# max10_bb.net
KiCad netlist of a schematic drawn in EAGLE
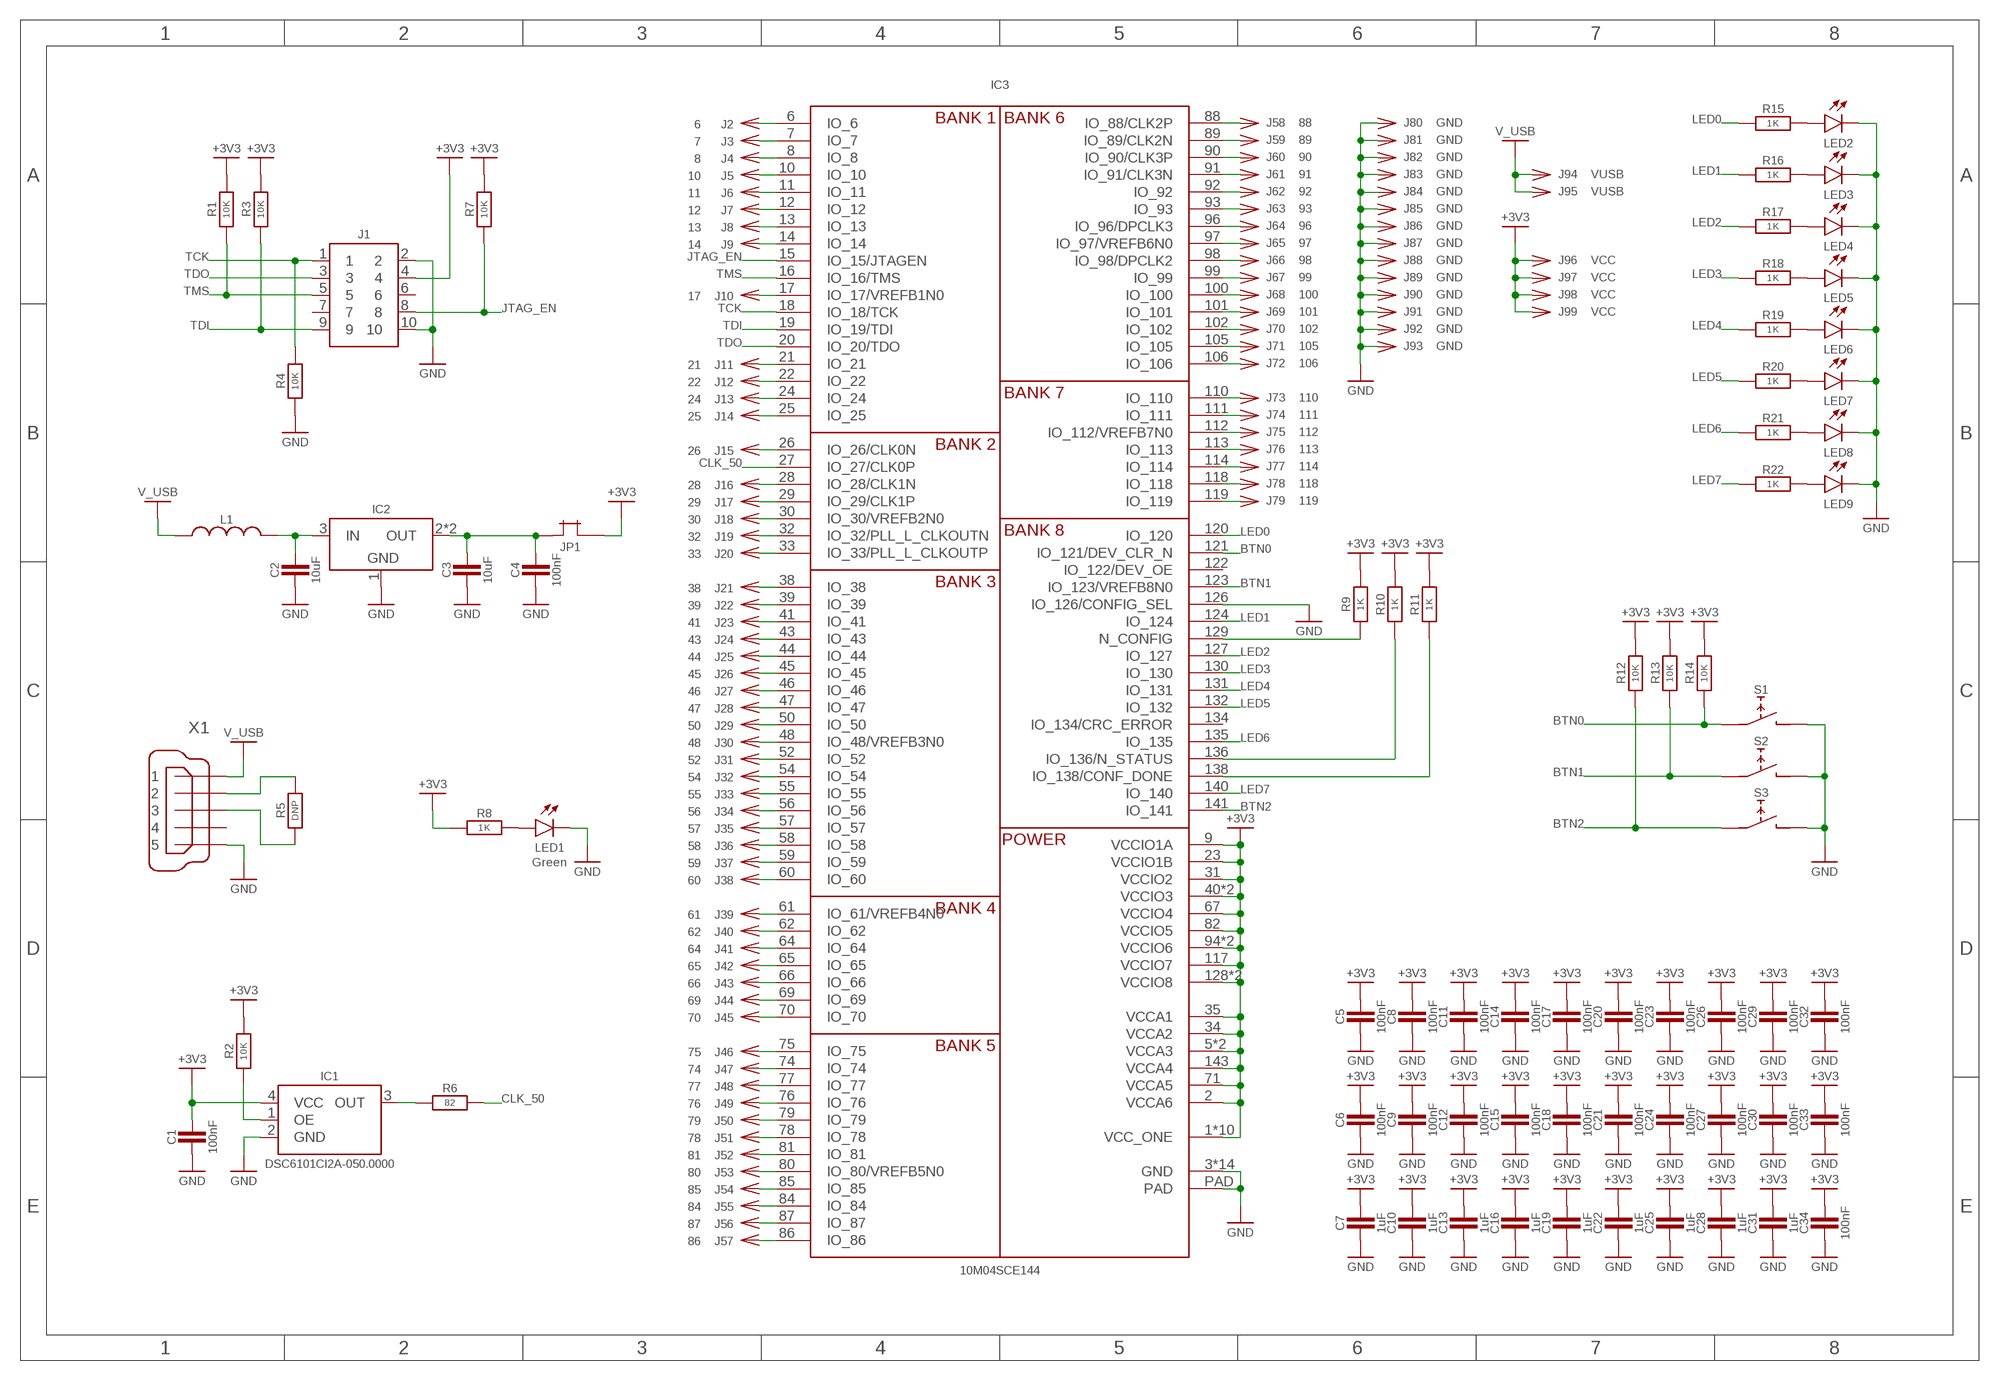
[diagram p0: schematic, sheet 1]

(export (version "E")
  (design (tool "Eeschema 10.0.6"))
  (components
    (comp (ref "C1")
      (value "100nF")
      (footprint "eagle-import:SMD0603")
      (libsource (lib "eagle-import") (part "C-0603"))
    )
    (comp (ref "C2")
      (value "10uF")
      (footprint "eagle-import:SMD0805")
      (libsource (lib "eagle-import") (part "C-0805"))
    )
    (comp (ref "C3")
      (value "10uF")
      (footprint "eagle-import:SMD0805")
      (libsource (lib "eagle-import") (part "C-0805"))
    )
    (comp (ref "C4")
      (value "100nF")
      (footprint "eagle-import:SMD0603")
      (libsource (lib "eagle-import") (part "C-0603"))
    )
    (comp (ref "C5")
      (value "100nF")
      (footprint "eagle-import:SMD0603")
      (libsource (lib "eagle-import") (part "C-0603"))
    )
    (comp (ref "C6")
      (value "100nF")
      (footprint "eagle-import:SMD0603")
      (libsource (lib "eagle-import") (part "C-0603"))
    )
    (comp (ref "C7")
      (value "1uF")
      (footprint "eagle-import:SMD0603")
      (libsource (lib "eagle-import") (part "C-0603"))
    )
    (comp (ref "C8")
      (value "100nF")
      (footprint "eagle-import:SMD0603")
      (libsource (lib "eagle-import") (part "C-0603"))
    )
    (comp (ref "C9")
      (value "100nF")
      (footprint "eagle-import:SMD0603")
      (libsource (lib "eagle-import") (part "C-0603"))
    )
    (comp (ref "C10")
      (value "1uF")
      (footprint "eagle-import:SMD0603")
      (libsource (lib "eagle-import") (part "C-0603"))
    )
    (comp (ref "C11")
      (value "100nF")
      (footprint "eagle-import:SMD0603")
      (libsource (lib "eagle-import") (part "C-0603"))
    )
    (comp (ref "C12")
      (value "100nF")
      (footprint "eagle-import:SMD0603")
      (libsource (lib "eagle-import") (part "C-0603"))
    )
    (comp (ref "C13")
      (value "1uF")
      (footprint "eagle-import:SMD0603")
      (libsource (lib "eagle-import") (part "C-0603"))
    )
    (comp (ref "C14")
      (value "100nF")
      (footprint "eagle-import:SMD0603")
      (libsource (lib "eagle-import") (part "C-0603"))
    )
    (comp (ref "C15")
      (value "100nF")
      (footprint "eagle-import:SMD0603")
      (libsource (lib "eagle-import") (part "C-0603"))
    )
    (comp (ref "C16")
      (value "1uF")
      (footprint "eagle-import:SMD0603")
      (libsource (lib "eagle-import") (part "C-0603"))
    )
    (comp (ref "C17")
      (value "100nF")
      (footprint "eagle-import:SMD0603")
      (libsource (lib "eagle-import") (part "C-0603"))
    )
    (comp (ref "C18")
      (value "100nF")
      (footprint "eagle-import:SMD0603")
      (libsource (lib "eagle-import") (part "C-0603"))
    )
    (comp (ref "C19")
      (value "1uF")
      (footprint "eagle-import:SMD0603")
      (libsource (lib "eagle-import") (part "C-0603"))
    )
    (comp (ref "C20")
      (value "100nF")
      (footprint "eagle-import:SMD0603")
      (libsource (lib "eagle-import") (part "C-0603"))
    )
    (comp (ref "C21")
      (value "100nF")
      (footprint "eagle-import:SMD0603")
      (libsource (lib "eagle-import") (part "C-0603"))
    )
    (comp (ref "C22")
      (value "1uF")
      (footprint "eagle-import:SMD0603")
      (libsource (lib "eagle-import") (part "C-0603"))
    )
    (comp (ref "C23")
      (value "100nF")
      (footprint "eagle-import:SMD0603")
      (libsource (lib "eagle-import") (part "C-0603"))
    )
    (comp (ref "C24")
      (value "100nF")
      (footprint "eagle-import:SMD0603")
      (libsource (lib "eagle-import") (part "C-0603"))
    )
    (comp (ref "C25")
      (value "1uF")
      (footprint "eagle-import:SMD0603")
      (libsource (lib "eagle-import") (part "C-0603"))
    )
    (comp (ref "C26")
      (value "100nF")
      (footprint "eagle-import:SMD0603")
      (libsource (lib "eagle-import") (part "C-0603"))
    )
    (comp (ref "C27")
      (value "100nF")
      (footprint "eagle-import:SMD0603")
      (libsource (lib "eagle-import") (part "C-0603"))
    )
    (comp (ref "C28")
      (value "1uF")
      (footprint "eagle-import:SMD0603")
      (libsource (lib "eagle-import") (part "C-0603"))
    )
    (comp (ref "C29")
      (value "100nF")
      (footprint "eagle-import:SMD0603")
      (libsource (lib "eagle-import") (part "C-0603"))
    )
    (comp (ref "C30")
      (value "100nF")
      (footprint "eagle-import:SMD0603")
      (libsource (lib "eagle-import") (part "C-0603"))
    )
    (comp (ref "C31")
      (value "1uF")
      (footprint "eagle-import:SMD0603")
      (libsource (lib "eagle-import") (part "C-0603"))
    )
    (comp (ref "C32")
      (value "100nF")
      (footprint "eagle-import:SMD0603")
      (libsource (lib "eagle-import") (part "C-0603"))
    )
    (comp (ref "C33")
      (value "100nF")
      (footprint "eagle-import:SMD0603")
      (libsource (lib "eagle-import") (part "C-0603"))
    )
    (comp (ref "C34")
      (value "100nF")
      (footprint "eagle-import:SMD0603")
      (libsource (lib "eagle-import") (part "C-0603"))
    )
    (comp (ref "IC1")
      (value "DSC6101CI2A-050.0000")
      (footprint "eagle-import:CDFN4")
      (libsource (lib "eagle-import") (part "OSC_EN-CDFN4"))
    )
    (comp (ref "IC2")
      (value "LM1117-SOT223")
      (footprint "eagle-import:SOT223")
      (libsource (lib "eagle-import") (part "LM1117-SOT223"))
    )
    (comp (ref "IC3")
      (value "10M04SCE144")
      (footprint "eagle-import:EQFP-144-0.5MM")
      (libsource (lib "eagle-import") (part "10M04SCE144"))
    )
    (comp (ref "J1")
      (value "HEADER-5X2-TH-2.54")
      (footprint "eagle-import:HEADER-5X2-2.54MM")
      (libsource (lib "eagle-import") (part "HEADER-5X2-TH-2.54"))
    )
    (comp (ref "J2")
      (value "6")
      (footprint "eagle-import:PIN-TH")
      (libsource (lib "eagle-import") (part "CONN-SINGLE-TH"))
    )
    (comp (ref "J3")
      (value "7")
      (footprint "eagle-import:PIN-TH")
      (libsource (lib "eagle-import") (part "CONN-SINGLE-TH"))
    )
    (comp (ref "J4")
      (value "8")
      (footprint "eagle-import:PIN-TH")
      (libsource (lib "eagle-import") (part "CONN-SINGLE-TH"))
    )
    (comp (ref "J5")
      (value "10")
      (footprint "eagle-import:PIN-TH")
      (libsource (lib "eagle-import") (part "CONN-SINGLE-TH"))
    )
    (comp (ref "J6")
      (value "11")
      (footprint "eagle-import:PIN-TH")
      (libsource (lib "eagle-import") (part "CONN-SINGLE-TH"))
    )
    (comp (ref "J7")
      (value "12")
      (footprint "eagle-import:PIN-TH")
      (libsource (lib "eagle-import") (part "CONN-SINGLE-TH"))
    )
    (comp (ref "J8")
      (value "13")
      (footprint "eagle-import:PIN-TH")
      (libsource (lib "eagle-import") (part "CONN-SINGLE-TH"))
    )
    (comp (ref "J9")
      (value "14")
      (footprint "eagle-import:PIN-TH")
      (libsource (lib "eagle-import") (part "CONN-SINGLE-TH"))
    )
    (comp (ref "J10")
      (value "17")
      (footprint "eagle-import:PIN-TH")
      (libsource (lib "eagle-import") (part "CONN-SINGLE-TH"))
    )
    (comp (ref "J11")
      (value "21")
      (footprint "eagle-import:PIN-TH")
      (libsource (lib "eagle-import") (part "CONN-SINGLE-TH"))
    )
    (comp (ref "J12")
      (value "22")
      (footprint "eagle-import:PIN-TH")
      (libsource (lib "eagle-import") (part "CONN-SINGLE-TH"))
    )
    (comp (ref "J13")
      (value "24")
      (footprint "eagle-import:PIN-TH")
      (libsource (lib "eagle-import") (part "CONN-SINGLE-TH"))
    )
    (comp (ref "J14")
      (value "25")
      (footprint "eagle-import:PIN-TH")
      (libsource (lib "eagle-import") (part "CONN-SINGLE-TH"))
    )
    (comp (ref "J15")
      (value "26")
      (footprint "eagle-import:PIN-TH")
      (libsource (lib "eagle-import") (part "CONN-SINGLE-TH"))
    )
    (comp (ref "J16")
      (value "28")
      (footprint "eagle-import:PIN-TH")
      (libsource (lib "eagle-import") (part "CONN-SINGLE-TH"))
    )
    (comp (ref "J17")
      (value "29")
      (footprint "eagle-import:PIN-TH")
      (libsource (lib "eagle-import") (part "CONN-SINGLE-TH"))
    )
    (comp (ref "J18")
      (value "30")
      (footprint "eagle-import:PIN-TH")
      (libsource (lib "eagle-import") (part "CONN-SINGLE-TH"))
    )
    (comp (ref "J19")
      (value "32")
      (footprint "eagle-import:PIN-TH")
      (libsource (lib "eagle-import") (part "CONN-SINGLE-TH"))
    )
    (comp (ref "J20")
      (value "33")
      (footprint "eagle-import:PIN-TH")
      (libsource (lib "eagle-import") (part "CONN-SINGLE-TH"))
    )
    (comp (ref "J21")
      (value "38")
      (footprint "eagle-import:PIN-TH")
      (libsource (lib "eagle-import") (part "CONN-SINGLE-TH"))
    )
    (comp (ref "J22")
      (value "39")
      (footprint "eagle-import:PIN-TH")
      (libsource (lib "eagle-import") (part "CONN-SINGLE-TH"))
    )
    (comp (ref "J23")
      (value "41")
      (footprint "eagle-import:PIN-TH")
      (libsource (lib "eagle-import") (part "CONN-SINGLE-TH"))
    )
    (comp (ref "J24")
      (value "43")
      (footprint "eagle-import:PIN-TH")
      (libsource (lib "eagle-import") (part "CONN-SINGLE-TH"))
    )
    (comp (ref "J25")
      (value "44")
      (footprint "eagle-import:PIN-TH")
      (libsource (lib "eagle-import") (part "CONN-SINGLE-TH"))
    )
    (comp (ref "J26")
      (value "45")
      (footprint "eagle-import:PIN-TH")
      (libsource (lib "eagle-import") (part "CONN-SINGLE-TH"))
    )
    (comp (ref "J27")
      (value "46")
      (footprint "eagle-import:PIN-TH")
      (libsource (lib "eagle-import") (part "CONN-SINGLE-TH"))
    )
    (comp (ref "J28")
      (value "47")
      (footprint "eagle-import:PIN-TH")
      (libsource (lib "eagle-import") (part "CONN-SINGLE-TH"))
    )
    (comp (ref "J29")
      (value "50")
      (footprint "eagle-import:PIN-TH")
      (libsource (lib "eagle-import") (part "CONN-SINGLE-TH"))
    )
    (comp (ref "J30")
      (value "48")
      (footprint "eagle-import:PIN-TH")
      (libsource (lib "eagle-import") (part "CONN-SINGLE-TH"))
    )
    (comp (ref "J31")
      (value "52")
      (footprint "eagle-import:PIN-TH")
      (libsource (lib "eagle-import") (part "CONN-SINGLE-TH"))
    )
    (comp (ref "J32")
      (value "54")
      (footprint "eagle-import:PIN-TH")
      (libsource (lib "eagle-import") (part "CONN-SINGLE-TH"))
    )
    (comp (ref "J33")
      (value "55")
      (footprint "eagle-import:PIN-TH")
      (libsource (lib "eagle-import") (part "CONN-SINGLE-TH"))
    )
    (comp (ref "J34")
      (value "56")
      (footprint "eagle-import:PIN-TH")
      (libsource (lib "eagle-import") (part "CONN-SINGLE-TH"))
    )
    (comp (ref "J35")
      (value "57")
      (footprint "eagle-import:PIN-TH")
      (libsource (lib "eagle-import") (part "CONN-SINGLE-TH"))
    )
    (comp (ref "J36")
      (value "58")
      (footprint "eagle-import:PIN-TH")
      (libsource (lib "eagle-import") (part "CONN-SINGLE-TH"))
    )
    (comp (ref "J37")
      (value "59")
      (footprint "eagle-import:PIN-TH")
      (libsource (lib "eagle-import") (part "CONN-SINGLE-TH"))
    )
    (comp (ref "J38")
      (value "60")
      (footprint "eagle-import:PIN-TH")
      (libsource (lib "eagle-import") (part "CONN-SINGLE-TH"))
    )
    (comp (ref "J39")
      (value "61")
      (footprint "eagle-import:PIN-TH")
      (libsource (lib "eagle-import") (part "CONN-SINGLE-TH"))
    )
    (comp (ref "J40")
      (value "62")
      (footprint "eagle-import:PIN-TH")
      (libsource (lib "eagle-import") (part "CONN-SINGLE-TH"))
    )
    (comp (ref "J41")
      (value "64")
      (footprint "eagle-import:PIN-TH")
      (libsource (lib "eagle-import") (part "CONN-SINGLE-TH"))
    )
    (comp (ref "J42")
      (value "65")
      (footprint "eagle-import:PIN-TH")
      (libsource (lib "eagle-import") (part "CONN-SINGLE-TH"))
    )
    (comp (ref "J43")
      (value "66")
      (footprint "eagle-import:PIN-TH")
      (libsource (lib "eagle-import") (part "CONN-SINGLE-TH"))
    )
    (comp (ref "J44")
      (value "69")
      (footprint "eagle-import:PIN-TH")
      (libsource (lib "eagle-import") (part "CONN-SINGLE-TH"))
    )
    (comp (ref "J45")
      (value "70")
      (footprint "eagle-import:PIN-TH")
      (libsource (lib "eagle-import") (part "CONN-SINGLE-TH"))
    )
    (comp (ref "J46")
      (value "75")
      (footprint "eagle-import:PIN-TH")
      (libsource (lib "eagle-import") (part "CONN-SINGLE-TH"))
    )
    (comp (ref "J47")
      (value "74")
      (footprint "eagle-import:PIN-TH")
      (libsource (lib "eagle-import") (part "CONN-SINGLE-TH"))
    )
    (comp (ref "J48")
      (value "77")
      (footprint "eagle-import:PIN-TH")
      (libsource (lib "eagle-import") (part "CONN-SINGLE-TH"))
    )
    (comp (ref "J49")
      (value "76")
      (footprint "eagle-import:PIN-TH")
      (libsource (lib "eagle-import") (part "CONN-SINGLE-TH"))
    )
    (comp (ref "J50")
      (value "79")
      (footprint "eagle-import:PIN-TH")
      (libsource (lib "eagle-import") (part "CONN-SINGLE-TH"))
    )
    (comp (ref "J51")
      (value "78")
      (footprint "eagle-import:PIN-TH")
      (libsource (lib "eagle-import") (part "CONN-SINGLE-TH"))
    )
    (comp (ref "J52")
      (value "81")
      (footprint "eagle-import:PIN-TH")
      (libsource (lib "eagle-import") (part "CONN-SINGLE-TH"))
    )
    (comp (ref "J53")
      (value "80")
      (footprint "eagle-import:PIN-TH")
      (libsource (lib "eagle-import") (part "CONN-SINGLE-TH"))
    )
    (comp (ref "J54")
      (value "85")
      (footprint "eagle-import:PIN-TH")
      (libsource (lib "eagle-import") (part "CONN-SINGLE-TH"))
    )
    (comp (ref "J55")
      (value "84")
      (footprint "eagle-import:PIN-TH")
      (libsource (lib "eagle-import") (part "CONN-SINGLE-TH"))
    )
    (comp (ref "J56")
      (value "87")
      (footprint "eagle-import:PIN-TH")
      (libsource (lib "eagle-import") (part "CONN-SINGLE-TH"))
    )
    (comp (ref "J57")
      (value "86")
      (footprint "eagle-import:PIN-TH")
      (libsource (lib "eagle-import") (part "CONN-SINGLE-TH"))
    )
    (comp (ref "J58")
      (value "88")
      (footprint "eagle-import:PIN-TH")
      (libsource (lib "eagle-import") (part "CONN-SINGLE-TH"))
    )
    (comp (ref "J59")
      (value "89")
      (footprint "eagle-import:PIN-TH")
      (libsource (lib "eagle-import") (part "CONN-SINGLE-TH"))
    )
    (comp (ref "J60")
      (value "90")
      (footprint "eagle-import:PIN-TH")
      (libsource (lib "eagle-import") (part "CONN-SINGLE-TH"))
    )
    (comp (ref "J61")
      (value "91")
      (footprint "eagle-import:PIN-TH")
      (libsource (lib "eagle-import") (part "CONN-SINGLE-TH"))
    )
    (comp (ref "J62")
      (value "92")
      (footprint "eagle-import:PIN-TH")
      (libsource (lib "eagle-import") (part "CONN-SINGLE-TH"))
    )
    (comp (ref "J63")
      (value "93")
      (footprint "eagle-import:PIN-TH")
      (libsource (lib "eagle-import") (part "CONN-SINGLE-TH"))
    )
    (comp (ref "J64")
      (value "96")
      (footprint "eagle-import:PIN-TH")
      (libsource (lib "eagle-import") (part "CONN-SINGLE-TH"))
    )
    (comp (ref "J65")
      (value "97")
      (footprint "eagle-import:PIN-TH")
      (libsource (lib "eagle-import") (part "CONN-SINGLE-TH"))
    )
    (comp (ref "J66")
      (value "98")
      (footprint "eagle-import:PIN-TH")
      (libsource (lib "eagle-import") (part "CONN-SINGLE-TH"))
    )
    (comp (ref "J67")
      (value "99")
      (footprint "eagle-import:PIN-TH")
      (libsource (lib "eagle-import") (part "CONN-SINGLE-TH"))
    )
    (comp (ref "J68")
      (value "100")
      (footprint "eagle-import:PIN-TH")
      (libsource (lib "eagle-import") (part "CONN-SINGLE-TH"))
    )
    (comp (ref "J69")
      (value "101")
      (footprint "eagle-import:PIN-TH")
      (libsource (lib "eagle-import") (part "CONN-SINGLE-TH"))
    )
    (comp (ref "J70")
      (value "102")
      (footprint "eagle-import:PIN-TH")
      (libsource (lib "eagle-import") (part "CONN-SINGLE-TH"))
    )
    (comp (ref "J71")
      (value "105")
      (footprint "eagle-import:PIN-TH")
      (libsource (lib "eagle-import") (part "CONN-SINGLE-TH"))
    )
    (comp (ref "J72")
      (value "106")
      (footprint "eagle-import:PIN-TH")
      (libsource (lib "eagle-import") (part "CONN-SINGLE-TH"))
    )
    (comp (ref "J73")
      (value "110")
      (footprint "eagle-import:PIN-TH")
      (libsource (lib "eagle-import") (part "CONN-SINGLE-TH"))
    )
    (comp (ref "J74")
      (value "111")
      (footprint "eagle-import:PIN-TH")
      (libsource (lib "eagle-import") (part "CONN-SINGLE-TH"))
    )
    (comp (ref "J75")
      (value "112")
      (footprint "eagle-import:PIN-TH")
      (libsource (lib "eagle-import") (part "CONN-SINGLE-TH"))
    )
    (comp (ref "J76")
      (value "113")
      (footprint "eagle-import:PIN-TH")
      (libsource (lib "eagle-import") (part "CONN-SINGLE-TH"))
    )
    (comp (ref "J77")
      (value "114")
      (footprint "eagle-import:PIN-TH")
      (libsource (lib "eagle-import") (part "CONN-SINGLE-TH"))
    )
    (comp (ref "J78")
      (value "118")
      (footprint "eagle-import:PIN-TH")
      (libsource (lib "eagle-import") (part "CONN-SINGLE-TH"))
    )
    (comp (ref "J79")
      (value "119")
      (footprint "eagle-import:PIN-TH")
      (libsource (lib "eagle-import") (part "CONN-SINGLE-TH"))
    )
    (comp (ref "J80")
      (value "GND")
      (footprint "eagle-import:PIN-TH")
      (libsource (lib "eagle-import") (part "CONN-SINGLE-TH"))
    )
    (comp (ref "J81")
      (value "GND")
      (footprint "eagle-import:PIN-TH")
      (libsource (lib "eagle-import") (part "CONN-SINGLE-TH"))
    )
    (comp (ref "J82")
      (value "GND")
      (footprint "eagle-import:PIN-TH")
      (libsource (lib "eagle-import") (part "CONN-SINGLE-TH"))
    )
    (comp (ref "J83")
      (value "GND")
      (footprint "eagle-import:PIN-TH")
      (libsource (lib "eagle-import") (part "CONN-SINGLE-TH"))
    )
    (comp (ref "J84")
      (value "GND")
      (footprint "eagle-import:PIN-TH")
      (libsource (lib "eagle-import") (part "CONN-SINGLE-TH"))
    )
    (comp (ref "J85")
      (value "GND")
      (footprint "eagle-import:PIN-TH")
      (libsource (lib "eagle-import") (part "CONN-SINGLE-TH"))
    )
    (comp (ref "J86")
      (value "GND")
      (footprint "eagle-import:PIN-TH")
      (libsource (lib "eagle-import") (part "CONN-SINGLE-TH"))
    )
    (comp (ref "J87")
      (value "GND")
      (footprint "eagle-import:PIN-TH")
      (libsource (lib "eagle-import") (part "CONN-SINGLE-TH"))
    )
    (comp (ref "J88")
      (value "GND")
      (footprint "eagle-import:PIN-TH")
      (libsource (lib "eagle-import") (part "CONN-SINGLE-TH"))
    )
    (comp (ref "J89")
      (value "GND")
      (footprint "eagle-import:PIN-TH")
      (libsource (lib "eagle-import") (part "CONN-SINGLE-TH"))
    )
    (comp (ref "J90")
      (value "GND")
      (footprint "eagle-import:PIN-TH")
      (libsource (lib "eagle-import") (part "CONN-SINGLE-TH"))
    )
    (comp (ref "J91")
      (value "GND")
      (footprint "eagle-import:PIN-TH")
      (libsource (lib "eagle-import") (part "CONN-SINGLE-TH"))
    )
    (comp (ref "J92")
      (value "GND")
      (footprint "eagle-import:PIN-TH")
      (libsource (lib "eagle-import") (part "CONN-SINGLE-TH"))
    )
    (comp (ref "J93")
      (value "GND")
      (footprint "eagle-import:PIN-TH")
      (libsource (lib "eagle-import") (part "CONN-SINGLE-TH"))
    )
    (comp (ref "J94")
      (value "VUSB")
      (footprint "eagle-import:PIN-TH")
      (libsource (lib "eagle-import") (part "CONN-SINGLE-TH"))
    )
    (comp (ref "J95")
      (value "VUSB")
      (footprint "eagle-import:PIN-TH")
      (libsource (lib "eagle-import") (part "CONN-SINGLE-TH"))
    )
    (comp (ref "J96")
      (value "VCC")
      (footprint "eagle-import:PIN-TH")
      (libsource (lib "eagle-import") (part "CONN-SINGLE-TH"))
    )
    (comp (ref "J97")
      (value "VCC")
      (footprint "eagle-import:PIN-TH")
      (libsource (lib "eagle-import") (part "CONN-SINGLE-TH"))
    )
    (comp (ref "J98")
      (value "VCC")
      (footprint "eagle-import:PIN-TH")
      (libsource (lib "eagle-import") (part "CONN-SINGLE-TH"))
    )
    (comp (ref "J99")
      (value "VCC")
      (footprint "eagle-import:PIN-TH")
      (libsource (lib "eagle-import") (part "CONN-SINGLE-TH"))
    )
    (comp (ref "JP1")
      (value "JUMPER-TH-TH")
      (footprint "eagle-import:JUMPER-TH")
      (libsource (lib "eagle-import") (part "JUMPER-TH-TH"))
    )
    (comp (ref "L1")
      (value "L-0603")
      (footprint "eagle-import:SMD0603")
      (libsource (lib "eagle-import") (part "L-0603"))
    )
    (comp (ref "LED1")
      (value "Green")
      (footprint "eagle-import:SMD0603")
      (libsource (lib "eagle-import") (part "LED_SMDLED_0603"))
    )
    (comp (ref "LED2")
      (value "LED_SMDLED_0603")
      (footprint "eagle-import:SMD0603")
      (libsource (lib "eagle-import") (part "LED_SMDLED_0603"))
    )
    (comp (ref "LED3")
      (value "LED_SMDLED_0603")
      (footprint "eagle-import:SMD0603")
      (libsource (lib "eagle-import") (part "LED_SMDLED_0603"))
    )
    (comp (ref "LED4")
      (value "LED_SMDLED_0603")
      (footprint "eagle-import:SMD0603")
      (libsource (lib "eagle-import") (part "LED_SMDLED_0603"))
    )
    (comp (ref "LED5")
      (value "LED_SMDLED_0603")
      (footprint "eagle-import:SMD0603")
      (libsource (lib "eagle-import") (part "LED_SMDLED_0603"))
    )
    (comp (ref "LED6")
      (value "LED_SMDLED_0603")
      (footprint "eagle-import:SMD0603")
      (libsource (lib "eagle-import") (part "LED_SMDLED_0603"))
    )
    (comp (ref "LED7")
      (value "LED_SMDLED_0603")
      (footprint "eagle-import:SMD0603")
      (libsource (lib "eagle-import") (part "LED_SMDLED_0603"))
    )
    (comp (ref "LED8")
      (value "LED_SMDLED_0603")
      (footprint "eagle-import:SMD0603")
      (libsource (lib "eagle-import") (part "LED_SMDLED_0603"))
    )
    (comp (ref "LED9")
      (value "LED_SMDLED_0603")
      (footprint "eagle-import:SMD0603")
      (libsource (lib "eagle-import") (part "LED_SMDLED_0603"))
    )
    (comp (ref "R1")
      (value "10K")
      (footprint "eagle-import:SMD0603")
      (libsource (lib "eagle-import") (part "R-0603"))
    )
    (comp (ref "R2")
      (value "10K")
      (footprint "eagle-import:SMD0603")
      (libsource (lib "eagle-import") (part "R-0603"))
    )
    (comp (ref "R3")
      (value "10K")
      (footprint "eagle-import:SMD0603")
      (libsource (lib "eagle-import") (part "R-0603"))
    )
    (comp (ref "R4")
      (value "10K")
      (footprint "eagle-import:SMD0603")
      (libsource (lib "eagle-import") (part "R-0603"))
    )
    (comp (ref "R5")
      (value "DNP")
      (footprint "eagle-import:SMD0603")
      (libsource (lib "eagle-import") (part "R-0603"))
    )
    (comp (ref "R6")
      (value "82")
      (footprint "eagle-import:SMD0603")
      (libsource (lib "eagle-import") (part "R-0603"))
    )
    (comp (ref "R7")
      (value "10K")
      (footprint "eagle-import:SMD0603")
      (libsource (lib "eagle-import") (part "R-0603"))
    )
    (comp (ref "R8")
      (value "1K")
      (footprint "eagle-import:SMD0603")
      (libsource (lib "eagle-import") (part "R-0603"))
    )
    (comp (ref "R9")
      (value "1K")
      (footprint "eagle-import:SMD0603")
      (libsource (lib "eagle-import") (part "R-0603"))
    )
    (comp (ref "R10")
      (value "1K")
      (footprint "eagle-import:SMD0603")
      (libsource (lib "eagle-import") (part "R-0603"))
    )
    (comp (ref "R11")
      (value "1K")
      (footprint "eagle-import:SMD0603")
      (libsource (lib "eagle-import") (part "R-0603"))
    )
    (comp (ref "R12")
      (value "10K")
      (footprint "eagle-import:SMD0603")
      (libsource (lib "eagle-import") (part "R-0603"))
    )
    (comp (ref "R13")
      (value "10K")
      (footprint "eagle-import:SMD0603")
      (libsource (lib "eagle-import") (part "R-0603"))
    )
    (comp (ref "R14")
      (value "10K")
      (footprint "eagle-import:SMD0603")
      (libsource (lib "eagle-import") (part "R-0603"))
    )
    (comp (ref "R15")
      (value "1K")
      (footprint "eagle-import:SMD0603")
      (libsource (lib "eagle-import") (part "R-0603"))
    )
    (comp (ref "R16")
      (value "1K")
      (footprint "eagle-import:SMD0603")
      (libsource (lib "eagle-import") (part "R-0603"))
    )
    (comp (ref "R17")
      (value "1K")
      (footprint "eagle-import:SMD0603")
      (libsource (lib "eagle-import") (part "R-0603"))
    )
    (comp (ref "R18")
      (value "1K")
      (footprint "eagle-import:SMD0603")
      (libsource (lib "eagle-import") (part "R-0603"))
    )
    (comp (ref "R19")
      (value "1K")
      (footprint "eagle-import:SMD0603")
      (libsource (lib "eagle-import") (part "R-0603"))
    )
    (comp (ref "R20")
      (value "1K")
      (footprint "eagle-import:SMD0603")
      (libsource (lib "eagle-import") (part "R-0603"))
    )
    (comp (ref "R21")
      (value "1K")
      (footprint "eagle-import:SMD0603")
      (libsource (lib "eagle-import") (part "R-0603"))
    )
    (comp (ref "R22")
      (value "1K")
      (footprint "eagle-import:SMD0603")
      (libsource (lib "eagle-import") (part "R-0603"))
    )
    (comp (ref "S1")
      (value "TACT_SWITCH_6MM-SMD")
      (footprint "eagle-import:TACT-SMD-6MM")
      (libsource (lib "eagle-import") (part "TACT_SWITCH_6MM-SMD"))
    )
    (comp (ref "S2")
      (value "TACT_SWITCH_6MM-SMD")
      (footprint "eagle-import:TACT-SMD-6MM")
      (libsource (lib "eagle-import") (part "TACT_SWITCH_6MM-SMD"))
    )
    (comp (ref "S3")
      (value "TACT_SWITCH_6MM-SMD")
      (footprint "eagle-import:TACT-SMD-6MM")
      (libsource (lib "eagle-import") (part "TACT_SWITCH_6MM-SMD"))
    )
    (comp (ref "X1")
      (value "MINI-USB-32005-201")
      (footprint "eagle-import:32005-201")
      (libsource (lib "eagle-import") (part "MINI-USB-32005-201"))
    )
  )
  (nets
    (net (code "1") (name "+3V3") (class "Default")
      (node (ref "C1") (pin "2") (pinfunction "2_2") (pintype "passive"))
      (node (ref "C10") (pin "2") (pinfunction "2_2") (pintype "passive"))
      (node (ref "C11") (pin "2") (pinfunction "2_2") (pintype "passive"))
      (node (ref "C12") (pin "2") (pinfunction "2_2") (pintype "passive"))
      (node (ref "C13") (pin "2") (pinfunction "2_2") (pintype "passive"))
      (node (ref "C14") (pin "2") (pinfunction "2_2") (pintype "passive"))
      (node (ref "C15") (pin "2") (pinfunction "2_2") (pintype "passive"))
      (node (ref "C16") (pin "2") (pinfunction "2_2") (pintype "passive"))
      (node (ref "C17") (pin "2") (pinfunction "2_2") (pintype "passive"))
      (node (ref "C18") (pin "2") (pinfunction "2_2") (pintype "passive"))
      (node (ref "C19") (pin "2") (pinfunction "2_2") (pintype "passive"))
      (node (ref "C20") (pin "2") (pinfunction "2_2") (pintype "passive"))
      (node (ref "C21") (pin "2") (pinfunction "2_2") (pintype "passive"))
      (node (ref "C22") (pin "2") (pinfunction "2_2") (pintype "passive"))
      (node (ref "C23") (pin "2") (pinfunction "2_2") (pintype "passive"))
      (node (ref "C24") (pin "2") (pinfunction "2_2") (pintype "passive"))
      (node (ref "C25") (pin "2") (pinfunction "2_2") (pintype "passive"))
      (node (ref "C26") (pin "2") (pinfunction "2_2") (pintype "passive"))
      (node (ref "C27") (pin "2") (pinfunction "2_2") (pintype "passive"))
      (node (ref "C28") (pin "2") (pinfunction "2_2") (pintype "passive"))
      (node (ref "C29") (pin "2") (pinfunction "2_2") (pintype "passive"))
      (node (ref "C30") (pin "2") (pinfunction "2_2") (pintype "passive"))
      (node (ref "C31") (pin "2") (pinfunction "2_2") (pintype "passive"))
      (node (ref "C32") (pin "2") (pinfunction "2_2") (pintype "passive"))
      (node (ref "C33") (pin "2") (pinfunction "2_2") (pintype "passive"))
      (node (ref "C34") (pin "2") (pinfunction "2_2") (pintype "passive"))
      (node (ref "C5") (pin "2") (pinfunction "2_2") (pintype "passive"))
      (node (ref "C6") (pin "2") (pinfunction "2_2") (pintype "passive"))
      (node (ref "C7") (pin "2") (pinfunction "2_2") (pintype "passive"))
      (node (ref "C8") (pin "2") (pinfunction "2_2") (pintype "passive"))
      (node (ref "C9") (pin "2") (pinfunction "2_2") (pintype "passive"))
      (node (ref "IC1") (pin "4") (pinfunction "VCC_4") (pintype "passive"))
      (node (ref "IC3") (pin "1") (pinfunction "VCC_ONE_1") (pintype "bidirectional"))
      (node (ref "IC3") (pin "103") (pinfunction "VCCIO6_103") (pintype "bidirectional"))
      (node (ref "IC3") (pin "107") (pinfunction "VCCA3_107") (pintype "bidirectional"))
      (node (ref "IC3") (pin "108") (pinfunction "VCC_ONE_108") (pintype "bidirectional"))
      (node (ref "IC3") (pin "109") (pinfunction "VCC_ONE_109") (pintype "bidirectional"))
      (node (ref "IC3") (pin "115") (pinfunction "VCC_ONE_115") (pintype "bidirectional"))
      (node (ref "IC3") (pin "117") (pinfunction "VCCIO7_117") (pintype "bidirectional"))
      (node (ref "IC3") (pin "128") (pinfunction "VCCIO8_128") (pintype "bidirectional"))
      (node (ref "IC3") (pin "139") (pinfunction "VCCIO8_139") (pintype "bidirectional"))
      (node (ref "IC3") (pin "143") (pinfunction "VCCA4_143") (pintype "bidirectional"))
      (node (ref "IC3") (pin "144") (pinfunction "VCC_ONE_144") (pintype "bidirectional"))
      (node (ref "IC3") (pin "2") (pinfunction "VCCA6_2") (pintype "bidirectional"))
      (node (ref "IC3") (pin "23") (pinfunction "VCCIO1B_23") (pintype "bidirectional"))
      (node (ref "IC3") (pin "31") (pinfunction "VCCIO2_31") (pintype "bidirectional"))
      (node (ref "IC3") (pin "34") (pinfunction "VCCA2_34") (pintype "bidirectional"))
      (node (ref "IC3") (pin "35") (pinfunction "VCCA1_35") (pintype "bidirectional"))
      (node (ref "IC3") (pin "36") (pinfunction "VCC_ONE_36") (pintype "bidirectional"))
      (node (ref "IC3") (pin "37") (pinfunction "VCC_ONE_37") (pintype "bidirectional"))
      (node (ref "IC3") (pin "40") (pinfunction "VCCIO3_40") (pintype "bidirectional"))
      (node (ref "IC3") (pin "49") (pinfunction "VCCIO3_49") (pintype "bidirectional"))
      (node (ref "IC3") (pin "5") (pinfunction "VCCA3_5") (pintype "bidirectional"))
      (node (ref "IC3") (pin "51") (pinfunction "VCC_ONE_51") (pintype "bidirectional"))
      (node (ref "IC3") (pin "67") (pinfunction "VCCIO4_67") (pintype "bidirectional"))
      (node (ref "IC3") (pin "71") (pinfunction "VCCA5_71") (pintype "bidirectional"))
      (node (ref "IC3") (pin "72") (pinfunction "VCC_ONE_72") (pintype "bidirectional"))
      (node (ref "IC3") (pin "73") (pinfunction "VCC_ONE_73") (pintype "bidirectional"))
      (node (ref "IC3") (pin "82") (pinfunction "VCCIO5_82") (pintype "bidirectional"))
      (node (ref "IC3") (pin "9") (pinfunction "VCCIO1A_9") (pintype "bidirectional"))
      (node (ref "IC3") (pin "94") (pinfunction "VCCIO6_94") (pintype "bidirectional"))
      (node (ref "J1") (pin "4") (pinfunction "4_4") (pintype "passive"))
      (node (ref "J96") (pin "1") (pinfunction "1_1") (pintype "passive"))
      (node (ref "J97") (pin "1") (pinfunction "1_1") (pintype "passive"))
      (node (ref "J98") (pin "1") (pinfunction "1_1") (pintype "passive"))
      (node (ref "J99") (pin "1") (pinfunction "1_1") (pintype "passive"))
      (node (ref "JP1") (pin "2") (pinfunction "2_2") (pintype "passive"))
      (node (ref "R1") (pin "2") (pinfunction "2_2") (pintype "passive"))
      (node (ref "R10") (pin "2") (pinfunction "2_2") (pintype "passive"))
      (node (ref "R11") (pin "2") (pinfunction "2_2") (pintype "passive"))
      (node (ref "R12") (pin "2") (pinfunction "2_2") (pintype "passive"))
      (node (ref "R13") (pin "2") (pinfunction "2_2") (pintype "passive"))
      (node (ref "R14") (pin "2") (pinfunction "2_2") (pintype "passive"))
      (node (ref "R2") (pin "2") (pinfunction "2_2") (pintype "passive"))
      (node (ref "R3") (pin "2") (pinfunction "2_2") (pintype "passive"))
      (node (ref "R7") (pin "2") (pinfunction "2_2") (pintype "passive"))
      (node (ref "R8") (pin "1") (pinfunction "1_1") (pintype "passive"))
      (node (ref "R9") (pin "2") (pinfunction "2_2") (pintype "passive"))
    )
    (net (code "2") (name "/BTN0") (class "Default")
      (node (ref "IC3") (pin "121") (pinfunction "IO_121/DEV_CLR_N_121") (pintype "bidirectional"))
      (node (ref "R14") (pin "1") (pinfunction "1_1") (pintype "passive"))
      (node (ref "S1") (pin "1") (pinfunction "1_1") (pintype "passive"))
      (node (ref "S1") (pin "2") (pinfunction "1_2") (pintype "passive"))
    )
    (net (code "3") (name "/BTN1") (class "Default")
      (node (ref "IC3") (pin "123") (pinfunction "IO_123/VREFB8N0_123") (pintype "bidirectional"))
      (node (ref "R13") (pin "1") (pinfunction "1_1") (pintype "passive"))
      (node (ref "S2") (pin "1") (pinfunction "1_1") (pintype "passive"))
      (node (ref "S2") (pin "2") (pinfunction "1_2") (pintype "passive"))
    )
    (net (code "4") (name "/BTN2") (class "Default")
      (node (ref "IC3") (pin "141") (pinfunction "IO_141_141") (pintype "bidirectional"))
      (node (ref "R12") (pin "1") (pinfunction "1_1") (pintype "passive"))
      (node (ref "S3") (pin "1") (pinfunction "1_1") (pintype "passive"))
      (node (ref "S3") (pin "2") (pinfunction "1_2") (pintype "passive"))
    )
    (net (code "5") (name "/CLK_50") (class "Default")
      (node (ref "IC3") (pin "27") (pinfunction "IO_27/CLK0P_27") (pintype "bidirectional"))
      (node (ref "R6") (pin "2") (pinfunction "2_2") (pintype "passive"))
    )
    (net (code "6") (name "/JTAG_EN") (class "Default")
      (node (ref "IC3") (pin "15") (pinfunction "IO_15/JTAGEN_15") (pintype "bidirectional"))
      (node (ref "J1") (pin "8") (pinfunction "8_8") (pintype "passive"))
      (node (ref "R7") (pin "1") (pinfunction "1_1") (pintype "passive"))
    )
    (net (code "7") (name "/LED0") (class "Default")
      (node (ref "IC3") (pin "120") (pinfunction "IO_120_120") (pintype "bidirectional"))
      (node (ref "R15") (pin "1") (pinfunction "1_1") (pintype "passive"))
    )
    (net (code "8") (name "/LED1") (class "Default")
      (node (ref "IC3") (pin "124") (pinfunction "IO_124_124") (pintype "bidirectional"))
      (node (ref "R16") (pin "1") (pinfunction "1_1") (pintype "passive"))
    )
    (net (code "9") (name "/LED2") (class "Default")
      (node (ref "IC3") (pin "127") (pinfunction "IO_127_127") (pintype "bidirectional"))
      (node (ref "R17") (pin "1") (pinfunction "1_1") (pintype "passive"))
    )
    (net (code "10") (name "/LED3") (class "Default")
      (node (ref "IC3") (pin "130") (pinfunction "IO_130_130") (pintype "bidirectional"))
      (node (ref "R18") (pin "1") (pinfunction "1_1") (pintype "passive"))
    )
    (net (code "11") (name "/LED4") (class "Default")
      (node (ref "IC3") (pin "131") (pinfunction "IO_131_131") (pintype "bidirectional"))
      (node (ref "R19") (pin "1") (pinfunction "1_1") (pintype "passive"))
    )
    (net (code "12") (name "/LED5") (class "Default")
      (node (ref "IC3") (pin "132") (pinfunction "IO_132_132") (pintype "bidirectional"))
      (node (ref "R20") (pin "1") (pinfunction "1_1") (pintype "passive"))
    )
    (net (code "13") (name "/LED6") (class "Default")
      (node (ref "IC3") (pin "135") (pinfunction "IO_135_135") (pintype "bidirectional"))
      (node (ref "R21") (pin "1") (pinfunction "1_1") (pintype "passive"))
    )
    (net (code "14") (name "/LED7") (class "Default")
      (node (ref "IC3") (pin "140") (pinfunction "IO_140_140") (pintype "bidirectional"))
      (node (ref "R22") (pin "1") (pinfunction "1_1") (pintype "passive"))
    )
    (net (code "15") (name "/TCK") (class "Default")
      (node (ref "IC3") (pin "18") (pinfunction "IO_18/TCK_18") (pintype "bidirectional"))
      (node (ref "J1") (pin "1") (pinfunction "1_1") (pintype "passive"))
      (node (ref "R4") (pin "2") (pinfunction "2_2") (pintype "passive"))
    )
    (net (code "16") (name "/TDI") (class "Default")
      (node (ref "IC3") (pin "19") (pinfunction "IO_19/TDI_19") (pintype "bidirectional"))
      (node (ref "J1") (pin "9") (pinfunction "9_9") (pintype "passive"))
      (node (ref "R3") (pin "1") (pinfunction "1_1") (pintype "passive"))
    )
    (net (code "17") (name "/TDO") (class "Default")
      (node (ref "IC3") (pin "20") (pinfunction "IO_20/TDO_20") (pintype "bidirectional"))
      (node (ref "J1") (pin "3") (pinfunction "3_3") (pintype "passive"))
    )
    (net (code "18") (name "/TMS") (class "Default")
      (node (ref "IC3") (pin "16") (pinfunction "IO_16/TMS_16") (pintype "bidirectional"))
      (node (ref "J1") (pin "5") (pinfunction "5_5") (pintype "passive"))
      (node (ref "R1") (pin "1") (pinfunction "1_1") (pintype "passive"))
    )
    (net (code "19") (name "GND") (class "Default")
      (node (ref "C1") (pin "1") (pinfunction "1_1") (pintype "passive"))
      (node (ref "C10") (pin "1") (pinfunction "1_1") (pintype "passive"))
      (node (ref "C11") (pin "1") (pinfunction "1_1") (pintype "passive"))
      (node (ref "C12") (pin "1") (pinfunction "1_1") (pintype "passive"))
      (node (ref "C13") (pin "1") (pinfunction "1_1") (pintype "passive"))
      (node (ref "C14") (pin "1") (pinfunction "1_1") (pintype "passive"))
      (node (ref "C15") (pin "1") (pinfunction "1_1") (pintype "passive"))
      (node (ref "C16") (pin "1") (pinfunction "1_1") (pintype "passive"))
      (node (ref "C17") (pin "1") (pinfunction "1_1") (pintype "passive"))
      (node (ref "C18") (pin "1") (pinfunction "1_1") (pintype "passive"))
      (node (ref "C19") (pin "1") (pinfunction "1_1") (pintype "passive"))
      (node (ref "C2") (pin "1") (pinfunction "1_1") (pintype "passive"))
      (node (ref "C20") (pin "1") (pinfunction "1_1") (pintype "passive"))
      (node (ref "C21") (pin "1") (pinfunction "1_1") (pintype "passive"))
      (node (ref "C22") (pin "1") (pinfunction "1_1") (pintype "passive"))
      (node (ref "C23") (pin "1") (pinfunction "1_1") (pintype "passive"))
      (node (ref "C24") (pin "1") (pinfunction "1_1") (pintype "passive"))
      (node (ref "C25") (pin "1") (pinfunction "1_1") (pintype "passive"))
      (node (ref "C26") (pin "1") (pinfunction "1_1") (pintype "passive"))
      (node (ref "C27") (pin "1") (pinfunction "1_1") (pintype "passive"))
      (node (ref "C28") (pin "1") (pinfunction "1_1") (pintype "passive"))
      (node (ref "C29") (pin "1") (pinfunction "1_1") (pintype "passive"))
      (node (ref "C3") (pin "1") (pinfunction "1_1") (pintype "passive"))
      (node (ref "C30") (pin "1") (pinfunction "1_1") (pintype "passive"))
      (node (ref "C31") (pin "1") (pinfunction "1_1") (pintype "passive"))
      (node (ref "C32") (pin "1") (pinfunction "1_1") (pintype "passive"))
      (node (ref "C33") (pin "1") (pinfunction "1_1") (pintype "passive"))
      (node (ref "C34") (pin "1") (pinfunction "1_1") (pintype "passive"))
      (node (ref "C4") (pin "1") (pinfunction "1_1") (pintype "passive"))
      (node (ref "C5") (pin "1") (pinfunction "1_1") (pintype "passive"))
      (node (ref "C6") (pin "1") (pinfunction "1_1") (pintype "passive"))
      (node (ref "C7") (pin "1") (pinfunction "1_1") (pintype "passive"))
      (node (ref "C8") (pin "1") (pinfunction "1_1") (pintype "passive"))
      (node (ref "C9") (pin "1") (pinfunction "1_1") (pintype "passive"))
      (node (ref "IC1") (pin "2") (pinfunction "GND_2") (pintype "passive"))
      (node (ref "IC2") (pin "1") (pinfunction "GND_1") (pintype "power_in"))
      (node (ref "IC3") (pin "104") (pinfunction "GND_104") (pintype "bidirectional"))
      (node (ref "IC3") (pin "116") (pinfunction "GND_116") (pintype "bidirectional"))
      (node (ref "IC3") (pin "125") (pinfunction "GND_125") (pintype "bidirectional"))
      (node (ref "IC3") (pin "126") (pinfunction "IO_126/CONFIG_SEL_126") (pintype "bidirectional"))
      (node (ref "IC3") (pin "133") (pinfunction "GND_133") (pintype "bidirectional"))
      (node (ref "IC3") (pin "137") (pinfunction "GND_137") (pintype "bidirectional"))
      (node (ref "IC3") (pin "142") (pinfunction "GND_142") (pintype "bidirectional"))
      (node (ref "IC3") (pin "3") (pinfunction "GND_3") (pintype "bidirectional"))
      (node (ref "IC3") (pin "4") (pinfunction "GND_4") (pintype "bidirectional"))
      (node (ref "IC3") (pin "42") (pinfunction "GND_42") (pintype "bidirectional"))
      (node (ref "IC3") (pin "53") (pinfunction "GND_53") (pintype "bidirectional"))
      (node (ref "IC3") (pin "63") (pinfunction "GND_63") (pintype "bidirectional"))
      (node (ref "IC3") (pin "68") (pinfunction "GND_68") (pintype "bidirectional"))
      (node (ref "IC3") (pin "83") (pinfunction "GND_83") (pintype "bidirectional"))
      (node (ref "IC3") (pin "95") (pinfunction "GND_95") (pintype "bidirectional"))
      (node (ref "IC3") (pin "PAD") (pinfunction "PAD_PAD") (pintype "bidirectional"))
      (node (ref "J1") (pin "10") (pinfunction "10_10") (pintype "passive"))
      (node (ref "J1") (pin "2") (pinfunction "2_2") (pintype "passive"))
      (node (ref "J80") (pin "1") (pinfunction "1_1") (pintype "passive"))
      (node (ref "J81") (pin "1") (pinfunction "1_1") (pintype "passive"))
      (node (ref "J82") (pin "1") (pinfunction "1_1") (pintype "passive"))
      (node (ref "J83") (pin "1") (pinfunction "1_1") (pintype "passive"))
      (node (ref "J84") (pin "1") (pinfunction "1_1") (pintype "passive"))
      (node (ref "J85") (pin "1") (pinfunction "1_1") (pintype "passive"))
      (node (ref "J86") (pin "1") (pinfunction "1_1") (pintype "passive"))
      (node (ref "J87") (pin "1") (pinfunction "1_1") (pintype "passive"))
      (node (ref "J88") (pin "1") (pinfunction "1_1") (pintype "passive"))
      (node (ref "J89") (pin "1") (pinfunction "1_1") (pintype "passive"))
      (node (ref "J90") (pin "1") (pinfunction "1_1") (pintype "passive"))
      (node (ref "J91") (pin "1") (pinfunction "1_1") (pintype "passive"))
      (node (ref "J92") (pin "1") (pinfunction "1_1") (pintype "passive"))
      (node (ref "J93") (pin "1") (pinfunction "1_1") (pintype "passive"))
      (node (ref "LED1") (pin "2") (pinfunction "C_2") (pintype "passive"))
      (node (ref "LED2") (pin "2") (pinfunction "C_2") (pintype "passive"))
      (node (ref "LED3") (pin "2") (pinfunction "C_2") (pintype "passive"))
      (node (ref "LED4") (pin "2") (pinfunction "C_2") (pintype "passive"))
      (node (ref "LED5") (pin "2") (pinfunction "C_2") (pintype "passive"))
      (node (ref "LED6") (pin "2") (pinfunction "C_2") (pintype "passive"))
      (node (ref "LED7") (pin "2") (pinfunction "C_2") (pintype "passive"))
      (node (ref "LED8") (pin "2") (pinfunction "C_2") (pintype "passive"))
      (node (ref "LED9") (pin "2") (pinfunction "C_2") (pintype "passive"))
      (node (ref "R4") (pin "1") (pinfunction "1_1") (pintype "passive"))
      (node (ref "S1") (pin "3") (pinfunction "2_3") (pintype "passive"))
      (node (ref "S1") (pin "4") (pinfunction "2_4") (pintype "passive"))
      (node (ref "S2") (pin "3") (pinfunction "2_3") (pintype "passive"))
      (node (ref "S2") (pin "4") (pinfunction "2_4") (pintype "passive"))
      (node (ref "S3") (pin "3") (pinfunction "2_3") (pintype "passive"))
      (node (ref "S3") (pin "4") (pinfunction "2_4") (pintype "passive"))
      (node (ref "X1") (pin "5") (pinfunction "5_5") (pintype "passive"))
    )
    (net (code "20") (name "Net-(C3-Pad2)") (class "Default")
      (node (ref "C3") (pin "2") (pinfunction "2_2") (pintype "passive"))
      (node (ref "C4") (pin "2") (pinfunction "2_2") (pintype "passive"))
      (node (ref "IC2") (pin "2") (pinfunction "OUT_2") (pintype "power_in"))
      (node (ref "IC2") (pin "4") (pinfunction "OUT_4") (pintype "power_in"))
      (node (ref "JP1") (pin "1") (pinfunction "1_1") (pintype "passive"))
    )
    (net (code "21") (name "Net-(IC1-OE)") (class "Default")
      (node (ref "IC1") (pin "1") (pinfunction "OE_1") (pintype "passive"))
      (node (ref "R2") (pin "1") (pinfunction "1_1") (pintype "passive"))
    )
    (net (code "22") (name "Net-(IC1-OUT)") (class "Default")
      (node (ref "IC1") (pin "3") (pinfunction "OUT_3") (pintype "passive"))
      (node (ref "R6") (pin "1") (pinfunction "1_1") (pintype "passive"))
    )
    (net (code "23") (name "Net-(IC2-IN)") (class "Default")
      (node (ref "C2") (pin "2") (pinfunction "2_2") (pintype "passive"))
      (node (ref "IC2") (pin "3") (pinfunction "IN_3") (pintype "power_in"))
      (node (ref "L1") (pin "2") (pinfunction "2_2") (pintype "passive"))
    )
    (net (code "24") (name "Net-(IC3-IO_6)") (class "Default")
      (node (ref "IC3") (pin "6") (pinfunction "IO_6_6") (pintype "bidirectional"))
      (node (ref "J2") (pin "1") (pinfunction "1_1") (pintype "passive"))
    )
    (net (code "25") (name "Net-(IC3-IO_7)") (class "Default")
      (node (ref "IC3") (pin "7") (pinfunction "IO_7_7") (pintype "bidirectional"))
      (node (ref "J3") (pin "1") (pinfunction "1_1") (pintype "passive"))
    )
    (net (code "26") (name "Net-(IC3-IO_8)") (class "Default")
      (node (ref "IC3") (pin "8") (pinfunction "IO_8_8") (pintype "bidirectional"))
      (node (ref "J4") (pin "1") (pinfunction "1_1") (pintype "passive"))
    )
    (net (code "27") (name "Net-(IC3-IO_10)") (class "Default")
      (node (ref "IC3") (pin "10") (pinfunction "IO_10_10") (pintype "bidirectional"))
      (node (ref "J5") (pin "1") (pinfunction "1_1") (pintype "passive"))
    )
    (net (code "28") (name "Net-(IC3-IO_11)") (class "Default")
      (node (ref "IC3") (pin "11") (pinfunction "IO_11_11") (pintype "bidirectional"))
      (node (ref "J6") (pin "1") (pinfunction "1_1") (pintype "passive"))
    )
    (net (code "29") (name "Net-(IC3-IO_12)") (class "Default")
      (node (ref "IC3") (pin "12") (pinfunction "IO_12_12") (pintype "bidirectional"))
      (node (ref "J7") (pin "1") (pinfunction "1_1") (pintype "passive"))
    )
    (net (code "30") (name "Net-(IC3-IO_13)") (class "Default")
      (node (ref "IC3") (pin "13") (pinfunction "IO_13_13") (pintype "bidirectional"))
      (node (ref "J8") (pin "1") (pinfunction "1_1") (pintype "passive"))
    )
    (net (code "31") (name "Net-(IC3-IO_14)") (class "Default")
      (node (ref "IC3") (pin "14") (pinfunction "IO_14_14") (pintype "bidirectional"))
      (node (ref "J9") (pin "1") (pinfunction "1_1") (pintype "passive"))
    )
    (net (code "32") (name "Net-(IC3-IO_17{slash}VREFB1N0)") (class "Default")
      (node (ref "IC3") (pin "17") (pinfunction "IO_17/VREFB1N0_17") (pintype "bidirectional"))
      (node (ref "J10") (pin "1") (pinfunction "1_1") (pintype "passive"))
    )
    (net (code "33") (name "Net-(IC3-IO_21)") (class "Default")
      (node (ref "IC3") (pin "21") (pinfunction "IO_21_21") (pintype "bidirectional"))
      (node (ref "J11") (pin "1") (pinfunction "1_1") (pintype "passive"))
    )
    (net (code "34") (name "Net-(IC3-IO_22)") (class "Default")
      (node (ref "IC3") (pin "22") (pinfunction "IO_22_22") (pintype "bidirectional"))
      (node (ref "J12") (pin "1") (pinfunction "1_1") (pintype "passive"))
    )
    (net (code "35") (name "Net-(IC3-IO_24)") (class "Default")
      (node (ref "IC3") (pin "24") (pinfunction "IO_24_24") (pintype "bidirectional"))
      (node (ref "J13") (pin "1") (pinfunction "1_1") (pintype "passive"))
    )
    (net (code "36") (name "Net-(IC3-IO_25)") (class "Default")
      (node (ref "IC3") (pin "25") (pinfunction "IO_25_25") (pintype "bidirectional"))
      (node (ref "J14") (pin "1") (pinfunction "1_1") (pintype "passive"))
    )
    (net (code "37") (name "Net-(IC3-IO_26{slash}CLK0N)") (class "Default")
      (node (ref "IC3") (pin "26") (pinfunction "IO_26/CLK0N_26") (pintype "bidirectional"))
      (node (ref "J15") (pin "1") (pinfunction "1_1") (pintype "passive"))
    )
    (net (code "38") (name "Net-(IC3-IO_28{slash}CLK1N)") (class "Default")
      (node (ref "IC3") (pin "28") (pinfunction "IO_28/CLK1N_28") (pintype "bidirectional"))
      (node (ref "J16") (pin "1") (pinfunction "1_1") (pintype "passive"))
    )
    (net (code "39") (name "Net-(IC3-IO_29{slash}CLK1P)") (class "Default")
      (node (ref "IC3") (pin "29") (pinfunction "IO_29/CLK1P_29") (pintype "bidirectional"))
      (node (ref "J17") (pin "1") (pinfunction "1_1") (pintype "passive"))
    )
    (net (code "40") (name "Net-(IC3-IO_30{slash}VREFB2N0)") (class "Default")
      (node (ref "IC3") (pin "30") (pinfunction "IO_30/VREFB2N0_30") (pintype "bidirectional"))
      (node (ref "J18") (pin "1") (pinfunction "1_1") (pintype "passive"))
    )
    (net (code "41") (name "Net-(IC3-IO_32{slash}PLL_L_CLKOUTN)") (class "Default")
      (node (ref "IC3") (pin "32") (pinfunction "IO_32/PLL_L_CLKOUTN_32") (pintype "bidirectional"))
      (node (ref "J19") (pin "1") (pinfunction "1_1") (pintype "passive"))
    )
    (net (code "42") (name "Net-(IC3-IO_33{slash}PLL_L_CLKOUTP)") (class "Default")
      (node (ref "IC3") (pin "33") (pinfunction "IO_33/PLL_L_CLKOUTP_33") (pintype "bidirectional"))
      (node (ref "J20") (pin "1") (pinfunction "1_1") (pintype "passive"))
    )
    (net (code "43") (name "Net-(IC3-IO_38)") (class "Default")
      (node (ref "IC3") (pin "38") (pinfunction "IO_38_38") (pintype "bidirectional"))
      (node (ref "J21") (pin "1") (pinfunction "1_1") (pintype "passive"))
    )
    (net (code "44") (name "Net-(IC3-IO_39)") (class "Default")
      (node (ref "IC3") (pin "39") (pinfunction "IO_39_39") (pintype "bidirectional"))
      (node (ref "J22") (pin "1") (pinfunction "1_1") (pintype "passive"))
    )
    (net (code "45") (name "Net-(IC3-IO_41)") (class "Default")
      (node (ref "IC3") (pin "41") (pinfunction "IO_41_41") (pintype "bidirectional"))
      (node (ref "J23") (pin "1") (pinfunction "1_1") (pintype "passive"))
    )
    (net (code "46") (name "Net-(IC3-IO_43)") (class "Default")
      (node (ref "IC3") (pin "43") (pinfunction "IO_43_43") (pintype "bidirectional"))
      (node (ref "J24") (pin "1") (pinfunction "1_1") (pintype "passive"))
    )
    (net (code "47") (name "Net-(IC3-IO_44)") (class "Default")
      (node (ref "IC3") (pin "44") (pinfunction "IO_44_44") (pintype "bidirectional"))
      (node (ref "J25") (pin "1") (pinfunction "1_1") (pintype "passive"))
    )
    (net (code "48") (name "Net-(IC3-IO_45)") (class "Default")
      (node (ref "IC3") (pin "45") (pinfunction "IO_45_45") (pintype "bidirectional"))
      (node (ref "J26") (pin "1") (pinfunction "1_1") (pintype "passive"))
    )
    (net (code "49") (name "Net-(IC3-IO_46)") (class "Default")
      (node (ref "IC3") (pin "46") (pinfunction "IO_46_46") (pintype "bidirectional"))
      (node (ref "J27") (pin "1") (pinfunction "1_1") (pintype "passive"))
    )
    (net (code "50") (name "Net-(IC3-IO_47)") (class "Default")
      (node (ref "IC3") (pin "47") (pinfunction "IO_47_47") (pintype "bidirectional"))
      (node (ref "J28") (pin "1") (pinfunction "1_1") (pintype "passive"))
    )
    (net (code "51") (name "Net-(IC3-IO_48{slash}VREFB3N0)") (class "Default")
      (node (ref "IC3") (pin "48") (pinfunction "IO_48/VREFB3N0_48") (pintype "bidirectional"))
      (node (ref "J30") (pin "1") (pinfunction "1_1") (pintype "passive"))
    )
    (net (code "52") (name "Net-(IC3-IO_50)") (class "Default")
      (node (ref "IC3") (pin "50") (pinfunction "IO_50_50") (pintype "bidirectional"))
      (node (ref "J29") (pin "1") (pinfunction "1_1") (pintype "passive"))
    )
    (net (code "53") (name "Net-(IC3-IO_52)") (class "Default")
      (node (ref "IC3") (pin "52") (pinfunction "IO_52_52") (pintype "bidirectional"))
      (node (ref "J31") (pin "1") (pinfunction "1_1") (pintype "passive"))
    )
    (net (code "54") (name "Net-(IC3-IO_54)") (class "Default")
      (node (ref "IC3") (pin "54") (pinfunction "IO_54_54") (pintype "bidirectional"))
      (node (ref "J32") (pin "1") (pinfunction "1_1") (pintype "passive"))
    )
    (net (code "55") (name "Net-(IC3-IO_55)") (class "Default")
      (node (ref "IC3") (pin "55") (pinfunction "IO_55_55") (pintype "bidirectional"))
      (node (ref "J33") (pin "1") (pinfunction "1_1") (pintype "passive"))
    )
    (net (code "56") (name "Net-(IC3-IO_56)") (class "Default")
      (node (ref "IC3") (pin "56") (pinfunction "IO_56_56") (pintype "bidirectional"))
      (node (ref "J34") (pin "1") (pinfunction "1_1") (pintype "passive"))
    )
    (net (code "57") (name "Net-(IC3-IO_57)") (class "Default")
      (node (ref "IC3") (pin "57") (pinfunction "IO_57_57") (pintype "bidirectional"))
      (node (ref "J35") (pin "1") (pinfunction "1_1") (pintype "passive"))
    )
    (net (code "58") (name "Net-(IC3-IO_58)") (class "Default")
      (node (ref "IC3") (pin "58") (pinfunction "IO_58_58") (pintype "bidirectional"))
      (node (ref "J36") (pin "1") (pinfunction "1_1") (pintype "passive"))
    )
    (net (code "59") (name "Net-(IC3-IO_59)") (class "Default")
      (node (ref "IC3") (pin "59") (pinfunction "IO_59_59") (pintype "bidirectional"))
      (node (ref "J37") (pin "1") (pinfunction "1_1") (pintype "passive"))
    )
    (net (code "60") (name "Net-(IC3-IO_60)") (class "Default")
      (node (ref "IC3") (pin "60") (pinfunction "IO_60_60") (pintype "bidirectional"))
      (node (ref "J38") (pin "1") (pinfunction "1_1") (pintype "passive"))
    )
    (net (code "61") (name "Net-(IC3-IO_61{slash}VREFB4N0)") (class "Default")
      (node (ref "IC3") (pin "61") (pinfunction "IO_61/VREFB4N0_61") (pintype "bidirectional"))
      (node (ref "J39") (pin "1") (pinfunction "1_1") (pintype "passive"))
    )
    (net (code "62") (name "Net-(IC3-IO_62)") (class "Default")
      (node (ref "IC3") (pin "62") (pinfunction "IO_62_62") (pintype "bidirectional"))
      (node (ref "J40") (pin "1") (pinfunction "1_1") (pintype "passive"))
    )
    (net (code "63") (name "Net-(IC3-IO_64)") (class "Default")
      (node (ref "IC3") (pin "64") (pinfunction "IO_64_64") (pintype "bidirectional"))
      (node (ref "J41") (pin "1") (pinfunction "1_1") (pintype "passive"))
    )
    (net (code "64") (name "Net-(IC3-IO_65)") (class "Default")
      (node (ref "IC3") (pin "65") (pinfunction "IO_65_65") (pintype "bidirectional"))
      (node (ref "J42") (pin "1") (pinfunction "1_1") (pintype "passive"))
    )
    (net (code "65") (name "Net-(IC3-IO_66)") (class "Default")
      (node (ref "IC3") (pin "66") (pinfunction "IO_66_66") (pintype "bidirectional"))
      (node (ref "J43") (pin "1") (pinfunction "1_1") (pintype "passive"))
    )
    (net (code "66") (name "Net-(IC3-IO_69)") (class "Default")
      (node (ref "IC3") (pin "69") (pinfunction "IO_69_69") (pintype "bidirectional"))
      (node (ref "J44") (pin "1") (pinfunction "1_1") (pintype "passive"))
    )
    (net (code "67") (name "Net-(IC3-IO_70)") (class "Default")
      (node (ref "IC3") (pin "70") (pinfunction "IO_70_70") (pintype "bidirectional"))
      (node (ref "J45") (pin "1") (pinfunction "1_1") (pintype "passive"))
    )
    (net (code "68") (name "Net-(IC3-IO_74)") (class "Default")
      (node (ref "IC3") (pin "74") (pinfunction "IO_74_74") (pintype "bidirectional"))
      (node (ref "J47") (pin "1") (pinfunction "1_1") (pintype "passive"))
    )
    (net (code "69") (name "Net-(IC3-IO_75)") (class "Default")
      (node (ref "IC3") (pin "75") (pinfunction "IO_75_75") (pintype "bidirectional"))
      (node (ref "J46") (pin "1") (pinfunction "1_1") (pintype "passive"))
    )
    (net (code "70") (name "Net-(IC3-IO_76)") (class "Default")
      (node (ref "IC3") (pin "76") (pinfunction "IO_76_76") (pintype "bidirectional"))
      (node (ref "J49") (pin "1") (pinfunction "1_1") (pintype "passive"))
    )
    (net (code "71") (name "Net-(IC3-IO_77)") (class "Default")
      (node (ref "IC3") (pin "77") (pinfunction "IO_77_77") (pintype "bidirectional"))
      (node (ref "J48") (pin "1") (pinfunction "1_1") (pintype "passive"))
    )
    (net (code "72") (name "Net-(IC3-IO_78)") (class "Default")
      (node (ref "IC3") (pin "78") (pinfunction "IO_78_78") (pintype "bidirectional"))
      (node (ref "J51") (pin "1") (pinfunction "1_1") (pintype "passive"))
    )
    (net (code "73") (name "Net-(IC3-IO_79)") (class "Default")
      (node (ref "IC3") (pin "79") (pinfunction "IO_79_79") (pintype "bidirectional"))
      (node (ref "J50") (pin "1") (pinfunction "1_1") (pintype "passive"))
    )
    (net (code "74") (name "Net-(IC3-IO_80{slash}VREFB5N0)") (class "Default")
      (node (ref "IC3") (pin "80") (pinfunction "IO_80/VREFB5N0_80") (pintype "bidirectional"))
      (node (ref "J53") (pin "1") (pinfunction "1_1") (pintype "passive"))
    )
    (net (code "75") (name "Net-(IC3-IO_81)") (class "Default")
      (node (ref "IC3") (pin "81") (pinfunction "IO_81_81") (pintype "bidirectional"))
      (node (ref "J52") (pin "1") (pinfunction "1_1") (pintype "passive"))
    )
    (net (code "76") (name "Net-(IC3-IO_84)") (class "Default")
      (node (ref "IC3") (pin "84") (pinfunction "IO_84_84") (pintype "bidirectional"))
      (node (ref "J55") (pin "1") (pinfunction "1_1") (pintype "passive"))
    )
    (net (code "77") (name "Net-(IC3-IO_85)") (class "Default")
      (node (ref "IC3") (pin "85") (pinfunction "IO_85_85") (pintype "bidirectional"))
      (node (ref "J54") (pin "1") (pinfunction "1_1") (pintype "passive"))
    )
    (net (code "78") (name "Net-(IC3-IO_86)") (class "Default")
      (node (ref "IC3") (pin "86") (pinfunction "IO_86_86") (pintype "bidirectional"))
      (node (ref "J57") (pin "1") (pinfunction "1_1") (pintype "passive"))
    )
    (net (code "79") (name "Net-(IC3-IO_87)") (class "Default")
      (node (ref "IC3") (pin "87") (pinfunction "IO_87_87") (pintype "bidirectional"))
      (node (ref "J56") (pin "1") (pinfunction "1_1") (pintype "passive"))
    )
    (net (code "80") (name "Net-(IC3-IO_88{slash}CLK2P)") (class "Default")
      (node (ref "IC3") (pin "88") (pinfunction "IO_88/CLK2P_88") (pintype "bidirectional"))
      (node (ref "J58") (pin "1") (pinfunction "1_1") (pintype "passive"))
    )
    (net (code "81") (name "Net-(IC3-IO_89{slash}CLK2N)") (class "Default")
      (node (ref "IC3") (pin "89") (pinfunction "IO_89/CLK2N_89") (pintype "bidirectional"))
      (node (ref "J59") (pin "1") (pinfunction "1_1") (pintype "passive"))
    )
    (net (code "82") (name "Net-(IC3-IO_90{slash}CLK3P)") (class "Default")
      (node (ref "IC3") (pin "90") (pinfunction "IO_90/CLK3P_90") (pintype "bidirectional"))
      (node (ref "J60") (pin "1") (pinfunction "1_1") (pintype "passive"))
    )
    (net (code "83") (name "Net-(IC3-IO_91{slash}CLK3N)") (class "Default")
      (node (ref "IC3") (pin "91") (pinfunction "IO_91/CLK3N_91") (pintype "bidirectional"))
      (node (ref "J61") (pin "1") (pinfunction "1_1") (pintype "passive"))
    )
    (net (code "84") (name "Net-(IC3-IO_92)") (class "Default")
      (node (ref "IC3") (pin "92") (pinfunction "IO_92_92") (pintype "bidirectional"))
      (node (ref "J62") (pin "1") (pinfunction "1_1") (pintype "passive"))
    )
    (net (code "85") (name "Net-(IC3-IO_93)") (class "Default")
      (node (ref "IC3") (pin "93") (pinfunction "IO_93_93") (pintype "bidirectional"))
      (node (ref "J63") (pin "1") (pinfunction "1_1") (pintype "passive"))
    )
    (net (code "86") (name "Net-(IC3-IO_96{slash}DPCLK3)") (class "Default")
      (node (ref "IC3") (pin "96") (pinfunction "IO_96/DPCLK3_96") (pintype "bidirectional"))
      (node (ref "J64") (pin "1") (pinfunction "1_1") (pintype "passive"))
    )
    (net (code "87") (name "Net-(IC3-IO_97{slash}VREFB6N0)") (class "Default")
      (node (ref "IC3") (pin "97") (pinfunction "IO_97/VREFB6N0_97") (pintype "bidirectional"))
      (node (ref "J65") (pin "1") (pinfunction "1_1") (pintype "passive"))
    )
    (net (code "88") (name "Net-(IC3-IO_98{slash}DPCLK2)") (class "Default")
      (node (ref "IC3") (pin "98") (pinfunction "IO_98/DPCLK2_98") (pintype "bidirectional"))
      (node (ref "J66") (pin "1") (pinfunction "1_1") (pintype "passive"))
    )
    (net (code "89") (name "Net-(IC3-IO_99)") (class "Default")
      (node (ref "IC3") (pin "99") (pinfunction "IO_99_99") (pintype "bidirectional"))
      (node (ref "J67") (pin "1") (pinfunction "1_1") (pintype "passive"))
    )
    (net (code "90") (name "Net-(IC3-IO_100)") (class "Default")
      (node (ref "IC3") (pin "100") (pinfunction "IO_100_100") (pintype "bidirectional"))
      (node (ref "J68") (pin "1") (pinfunction "1_1") (pintype "passive"))
    )
    (net (code "91") (name "Net-(IC3-IO_101)") (class "Default")
      (node (ref "IC3") (pin "101") (pinfunction "IO_101_101") (pintype "bidirectional"))
      (node (ref "J69") (pin "1") (pinfunction "1_1") (pintype "passive"))
    )
    (net (code "92") (name "Net-(IC3-IO_102)") (class "Default")
      (node (ref "IC3") (pin "102") (pinfunction "IO_102_102") (pintype "bidirectional"))
      (node (ref "J70") (pin "1") (pinfunction "1_1") (pintype "passive"))
    )
    (net (code "93") (name "Net-(IC3-IO_105)") (class "Default")
      (node (ref "IC3") (pin "105") (pinfunction "IO_105_105") (pintype "bidirectional"))
      (node (ref "J71") (pin "1") (pinfunction "1_1") (pintype "passive"))
    )
    (net (code "94") (name "Net-(IC3-IO_106)") (class "Default")
      (node (ref "IC3") (pin "106") (pinfunction "IO_106_106") (pintype "bidirectional"))
      (node (ref "J72") (pin "1") (pinfunction "1_1") (pintype "passive"))
    )
    (net (code "95") (name "Net-(IC3-IO_110)") (class "Default")
      (node (ref "IC3") (pin "110") (pinfunction "IO_110_110") (pintype "bidirectional"))
      (node (ref "J73") (pin "1") (pinfunction "1_1") (pintype "passive"))
    )
    (net (code "96") (name "Net-(IC3-IO_111)") (class "Default")
      (node (ref "IC3") (pin "111") (pinfunction "IO_111_111") (pintype "bidirectional"))
      (node (ref "J74") (pin "1") (pinfunction "1_1") (pintype "passive"))
    )
    (net (code "97") (name "Net-(IC3-IO_112{slash}VREFB7N0)") (class "Default")
      (node (ref "IC3") (pin "112") (pinfunction "IO_112/VREFB7N0_112") (pintype "bidirectional"))
      (node (ref "J75") (pin "1") (pinfunction "1_1") (pintype "passive"))
    )
    (net (code "98") (name "Net-(IC3-IO_113)") (class "Default")
      (node (ref "IC3") (pin "113") (pinfunction "IO_113_113") (pintype "bidirectional"))
      (node (ref "J76") (pin "1") (pinfunction "1_1") (pintype "passive"))
    )
    (net (code "99") (name "Net-(IC3-IO_114)") (class "Default")
      (node (ref "IC3") (pin "114") (pinfunction "IO_114_114") (pintype "bidirectional"))
      (node (ref "J77") (pin "1") (pinfunction "1_1") (pintype "passive"))
    )
    (net (code "100") (name "Net-(IC3-IO_118)") (class "Default")
      (node (ref "IC3") (pin "118") (pinfunction "IO_118_118") (pintype "bidirectional"))
      (node (ref "J78") (pin "1") (pinfunction "1_1") (pintype "passive"))
    )
    (net (code "101") (name "Net-(IC3-IO_119)") (class "Default")
      (node (ref "IC3") (pin "119") (pinfunction "IO_119_119") (pintype "bidirectional"))
      (node (ref "J79") (pin "1") (pinfunction "1_1") (pintype "passive"))
    )
    (net (code "102") (name "Net-(IC3-IO_136{slash}N_STATUS)") (class "Default")
      (node (ref "IC3") (pin "136") (pinfunction "IO_136/N_STATUS_136") (pintype "bidirectional"))
      (node (ref "R10") (pin "1") (pinfunction "1_1") (pintype "passive"))
    )
    (net (code "103") (name "Net-(IC3-IO_138{slash}CONF_DONE)") (class "Default")
      (node (ref "IC3") (pin "138") (pinfunction "IO_138/CONF_DONE_138") (pintype "bidirectional"))
      (node (ref "R11") (pin "1") (pinfunction "1_1") (pintype "passive"))
    )
    (net (code "104") (name "Net-(IC3-N_CONFIG)") (class "Default")
      (node (ref "IC3") (pin "129") (pinfunction "N_CONFIG_129") (pintype "bidirectional"))
      (node (ref "R9") (pin "1") (pinfunction "1_1") (pintype "passive"))
    )
    (net (code "105") (name "Net-(LED1-A)") (class "Default")
      (node (ref "LED1") (pin "1") (pinfunction "A_1") (pintype "passive"))
      (node (ref "R8") (pin "2") (pinfunction "2_2") (pintype "passive"))
    )
    (net (code "106") (name "Net-(LED2-A)") (class "Default")
      (node (ref "LED2") (pin "1") (pinfunction "A_1") (pintype "passive"))
      (node (ref "R15") (pin "2") (pinfunction "2_2") (pintype "passive"))
    )
    (net (code "107") (name "Net-(LED3-A)") (class "Default")
      (node (ref "LED3") (pin "1") (pinfunction "A_1") (pintype "passive"))
      (node (ref "R16") (pin "2") (pinfunction "2_2") (pintype "passive"))
    )
    (net (code "108") (name "Net-(LED4-A)") (class "Default")
      (node (ref "LED4") (pin "1") (pinfunction "A_1") (pintype "passive"))
      (node (ref "R17") (pin "2") (pinfunction "2_2") (pintype "passive"))
    )
    (net (code "109") (name "Net-(LED5-A)") (class "Default")
      (node (ref "LED5") (pin "1") (pinfunction "A_1") (pintype "passive"))
      (node (ref "R18") (pin "2") (pinfunction "2_2") (pintype "passive"))
    )
    (net (code "110") (name "Net-(LED6-A)") (class "Default")
      (node (ref "LED6") (pin "1") (pinfunction "A_1") (pintype "passive"))
      (node (ref "R19") (pin "2") (pinfunction "2_2") (pintype "passive"))
    )
    (net (code "111") (name "Net-(LED7-A)") (class "Default")
      (node (ref "LED7") (pin "1") (pinfunction "A_1") (pintype "passive"))
      (node (ref "R20") (pin "2") (pinfunction "2_2") (pintype "passive"))
    )
    (net (code "112") (name "Net-(LED8-A)") (class "Default")
      (node (ref "LED8") (pin "1") (pinfunction "A_1") (pintype "passive"))
      (node (ref "R21") (pin "2") (pinfunction "2_2") (pintype "passive"))
    )
    (net (code "113") (name "Net-(LED9-A)") (class "Default")
      (node (ref "LED9") (pin "1") (pinfunction "A_1") (pintype "passive"))
      (node (ref "R22") (pin "2") (pinfunction "2_2") (pintype "passive"))
    )
    (net (code "114") (name "Net-(R5-Pad1)") (class "Default")
      (node (ref "R5") (pin "1") (pinfunction "1_1") (pintype "passive"))
      (node (ref "X1") (pin "3") (pinfunction "3_3") (pintype "passive"))
    )
    (net (code "115") (name "Net-(R5-Pad2)") (class "Default")
      (node (ref "R5") (pin "2") (pinfunction "2_2") (pintype "passive"))
      (node (ref "X1") (pin "2") (pinfunction "2_2") (pintype "passive"))
    )
    (net (code "116") (name "V_USB") (class "Default")
      (node (ref "J94") (pin "1") (pinfunction "1_1") (pintype "passive"))
      (node (ref "J95") (pin "1") (pinfunction "1_1") (pintype "passive"))
      (node (ref "L1") (pin "1") (pinfunction "1_1") (pintype "passive"))
      (node (ref "X1") (pin "1") (pinfunction "1_1") (pintype "passive"))
    )
    (net (code "117") (name "unconnected-(IC3-IO_122{slash}DEV_OE-Pad122)") (class "Default")
      (node (ref "IC3") (pin "122") (pinfunction "IO_122/DEV_OE_122") (pintype "bidirectional"))
    )
    (net (code "118") (name "unconnected-(IC3-IO_134{slash}CRC_ERROR-Pad134)") (class "Default")
      (node (ref "IC3") (pin "134") (pinfunction "IO_134/CRC_ERROR_134") (pintype "bidirectional"))
    )
    (net (code "119") (name "unconnected-(J1-Pad6)") (class "Default")
      (node (ref "J1") (pin "6") (pinfunction "6_6") (pintype "passive"))
    )
    (net (code "120") (name "unconnected-(J1-Pad7)") (class "Default")
      (node (ref "J1") (pin "7") (pinfunction "7_7") (pintype "passive"))
    )
    (net (code "121") (name "unconnected-(X1-Pad4)") (class "Default")
      (node (ref "X1") (pin "4") (pinfunction "4_4") (pintype "passive"))
    )
  )
)
